# Ali_CC_Regolabile_OpAmp_NPN.net
KiCad netlist of a schematic drawn in EAGLE
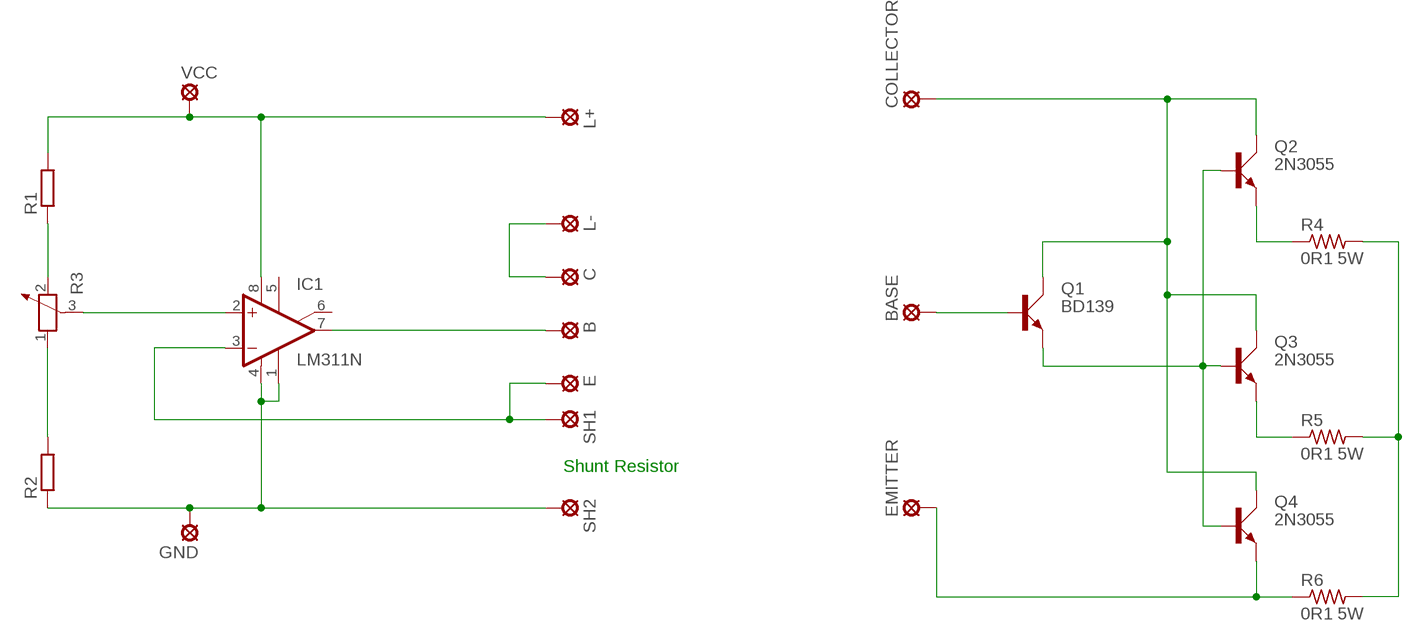
[diagram p0: schematic, sheet 1]

(export (version "E")
  (design (tool "Eeschema 10.0.6"))
  (components
    (comp (ref "B")
      (value "SE14")
      (footprint "eagle-import:SE14")
      (libsource (lib "eagle-import") (part "SE14"))
    )
    (comp (ref "BASE")
      (value "SE14")
      (footprint "eagle-import:SE14")
      (libsource (lib "eagle-import") (part "SE14"))
    )
    (comp (ref "C")
      (value "SE14")
      (footprint "eagle-import:SE14")
      (libsource (lib "eagle-import") (part "SE14"))
    )
    (comp (ref "COLLECTOR")
      (value "SE14")
      (footprint "eagle-import:SE14")
      (libsource (lib "eagle-import") (part "SE14"))
    )
    (comp (ref "E")
      (value "SE14")
      (footprint "eagle-import:SE14")
      (libsource (lib "eagle-import") (part "SE14"))
    )
    (comp (ref "EMITTER")
      (value "SE14")
      (footprint "eagle-import:SE14")
      (libsource (lib "eagle-import") (part "SE14"))
    )
    (comp (ref "GND")
      (value "SE14")
      (footprint "eagle-import:SE14")
      (libsource (lib "eagle-import") (part "SE14"))
    )
    (comp (ref "IC1")
      (value "LM311N")
      (footprint "eagle-import:DIL08")
      (libsource (lib "eagle-import") (part "LM311N"))
    )
    (comp (ref "L+")
      (value "SE14")
      (footprint "eagle-import:SE14")
      (libsource (lib "eagle-import") (part "SE14"))
    )
    (comp (ref "L-")
      (value "SE14")
      (footprint "eagle-import:SE14")
      (libsource (lib "eagle-import") (part "SE14"))
    )
    (comp (ref "Q1")
      (value "BD139")
      (footprint "eagle-import:TO126AV")
      (libsource (lib "eagle-import") (part "BD139"))
    )
    (comp (ref "Q2")
      (value "2N3055")
      (footprint "eagle-import:TO3A")
      (libsource (lib "eagle-import") (part "2N3055"))
    )
    (comp (ref "Q3")
      (value "2N3055")
      (footprint "eagle-import:TO3A")
      (libsource (lib "eagle-import") (part "2N3055"))
    )
    (comp (ref "Q4")
      (value "2N3055")
      (footprint "eagle-import:TO3A")
      (libsource (lib "eagle-import") (part "2N3055"))
    )
    (comp (ref "R1")
      (value "R-EU_0207/12")
      (footprint "eagle-import:0207_12")
      (libsource (lib "eagle-import") (part "R-EU_0207/12"))
    )
    (comp (ref "R2")
      (value "R-EU_0207/12")
      (footprint "eagle-import:0207_12")
      (libsource (lib "eagle-import") (part "R-EU_0207/12"))
    )
    (comp (ref "R3")
      (value "POTENTIOMETER_PT-10")
      (footprint "eagle-import:PT-10")
      (libsource (lib "eagle-import") (part "POTENTIOMETER_PT-10"))
    )
    (comp (ref "R4")
      (value "0R1 5W")
      (footprint "eagle-import:0617_22")
      (libsource (lib "eagle-import") (part "R-US_0617/22"))
    )
    (comp (ref "R5")
      (value "0R1 5W")
      (footprint "eagle-import:0617_22")
      (libsource (lib "eagle-import") (part "R-US_0617/22"))
    )
    (comp (ref "R6")
      (value "0R1 5W")
      (footprint "eagle-import:0617_22")
      (libsource (lib "eagle-import") (part "R-US_0617/22"))
    )
    (comp (ref "SH1")
      (value "SE14")
      (footprint "eagle-import:SE14")
      (libsource (lib "eagle-import") (part "SE14"))
    )
    (comp (ref "SH2")
      (value "SE14")
      (footprint "eagle-import:SE14")
      (libsource (lib "eagle-import") (part "SE14"))
    )
    (comp (ref "VCC")
      (value "SE14")
      (footprint "eagle-import:SE14")
      (libsource (lib "eagle-import") (part "SE14"))
    )
  )
  (nets
    (net (code "1") (name "Net-(BASE-PadMP)") (class "Default")
      (node (ref "BASE") (pin "MP") (pinfunction "MP_MP") (pintype "passive"))
      (node (ref "Q1") (pin "B") (pinfunction "B_B") (pintype "passive"))
    )
    (net (code "2") (name "Net-(C-PadMP)") (class "Default")
      (node (ref "C") (pin "MP") (pinfunction "MP_MP") (pintype "passive"))
      (node (ref "L-") (pin "MP") (pinfunction "MP_MP") (pintype "passive"))
    )
    (net (code "3") (name "Net-(COLLECTOR-PadMP)") (class "Default")
      (node (ref "COLLECTOR") (pin "MP") (pinfunction "MP_MP") (pintype "passive"))
      (node (ref "Q1") (pin "C") (pinfunction "C_C") (pintype "passive"))
      (node (ref "Q2") (pin "C") (pinfunction "C_C") (pintype "passive"))
      (node (ref "Q2") (pin "C1") (pinfunction "C_C1") (pintype "passive"))
      (node (ref "Q3") (pin "C") (pinfunction "C_C") (pintype "passive"))
      (node (ref "Q3") (pin "C1") (pinfunction "C_C1") (pintype "passive"))
      (node (ref "Q4") (pin "C") (pinfunction "C_C") (pintype "passive"))
      (node (ref "Q4") (pin "C1") (pinfunction "C_C1") (pintype "passive"))
    )
    (net (code "4") (name "Net-(EMITTER-PadMP)") (class "Default")
      (node (ref "EMITTER") (pin "MP") (pinfunction "MP_MP") (pintype "passive"))
      (node (ref "Q4") (pin "E") (pinfunction "E_E") (pintype "passive"))
      (node (ref "R6") (pin "1") (pinfunction "1_1") (pintype "passive"))
    )
    (net (code "5") (name "Net-(IC1-+IN)") (class "Default")
      (node (ref "IC1") (pin "2") (pinfunction "+IN_2") (pintype "input"))
      (node (ref "R3") (pin "3") (pinfunction "3_3") (pintype "passive"))
    )
    (net (code "6") (name "Net-(IC1--IN)") (class "Default")
      (node (ref "E") (pin "MP") (pinfunction "MP_MP") (pintype "passive"))
      (node (ref "IC1") (pin "3") (pinfunction "-IN_3") (pintype "input"))
      (node (ref "SH1") (pin "MP") (pinfunction "MP_MP") (pintype "passive"))
    )
    (net (code "7") (name "Net-(IC1-GND)") (class "Default")
      (node (ref "GND") (pin "MP") (pinfunction "MP_MP") (pintype "passive"))
      (node (ref "IC1") (pin "1") (pinfunction "GND_1") (pintype "passive"))
      (node (ref "IC1") (pin "4") (pinfunction "V-_4") (pintype "power_in"))
      (node (ref "R2") (pin "1") (pinfunction "1_1") (pintype "passive"))
      (node (ref "SH2") (pin "MP") (pinfunction "MP_MP") (pintype "passive"))
    )
    (net (code "8") (name "Net-(IC1-OUT)") (class "Default")
      (node (ref "B") (pin "MP") (pinfunction "MP_MP") (pintype "passive"))
      (node (ref "IC1") (pin "7") (pinfunction "OUT_7") (pintype "output"))
    )
    (net (code "9") (name "Net-(IC1-V+)") (class "Default")
      (node (ref "IC1") (pin "8") (pinfunction "V+_8") (pintype "power_in"))
      (node (ref "L+") (pin "MP") (pinfunction "MP_MP") (pintype "passive"))
      (node (ref "R1") (pin "2") (pinfunction "2_2") (pintype "passive"))
      (node (ref "VCC") (pin "MP") (pinfunction "MP_MP") (pintype "passive"))
    )
    (net (code "10") (name "Net-(Q1-PadE)") (class "Default")
      (node (ref "Q1") (pin "E") (pinfunction "E_E") (pintype "passive"))
      (node (ref "Q2") (pin "B") (pinfunction "B_B") (pintype "passive"))
      (node (ref "Q3") (pin "B") (pinfunction "B_B") (pintype "passive"))
      (node (ref "Q4") (pin "B") (pinfunction "B_B") (pintype "passive"))
    )
    (net (code "11") (name "Net-(Q2-PadE)") (class "Default")
      (node (ref "Q2") (pin "E") (pinfunction "E_E") (pintype "passive"))
      (node (ref "R4") (pin "1") (pinfunction "1_1") (pintype "passive"))
    )
    (net (code "12") (name "Net-(Q3-PadE)") (class "Default")
      (node (ref "Q3") (pin "E") (pinfunction "E_E") (pintype "passive"))
      (node (ref "R5") (pin "1") (pinfunction "1_1") (pintype "passive"))
    )
    (net (code "13") (name "Net-(R1-Pad1)") (class "Default")
      (node (ref "R1") (pin "1") (pinfunction "1_1") (pintype "passive"))
      (node (ref "R3") (pin "2") (pinfunction "2_2") (pintype "passive"))
    )
    (net (code "14") (name "Net-(R2-Pad2)") (class "Default")
      (node (ref "R2") (pin "2") (pinfunction "2_2") (pintype "passive"))
      (node (ref "R3") (pin "1") (pinfunction "1_1") (pintype "passive"))
    )
    (net (code "15") (name "Net-(R4-Pad2)") (class "Default")
      (node (ref "R4") (pin "2") (pinfunction "2_2") (pintype "passive"))
      (node (ref "R5") (pin "2") (pinfunction "2_2") (pintype "passive"))
      (node (ref "R6") (pin "2") (pinfunction "2_2") (pintype "passive"))
    )
    (net (code "16") (name "unconnected-(IC1-ON-Pad5)") (class "Default")
      (node (ref "IC1") (pin "5") (pinfunction "ON_5") (pintype "passive"))
    )
    (net (code "17") (name "unconnected-(IC1-ON{slash}STR-Pad6)") (class "Default")
      (node (ref "IC1") (pin "6") (pinfunction "ON/STR_6") (pintype "passive"))
    )
  )
)
